# ADC_Chip_And_ISO.net
KiCad netlist of a schematic drawn in Altium Designer
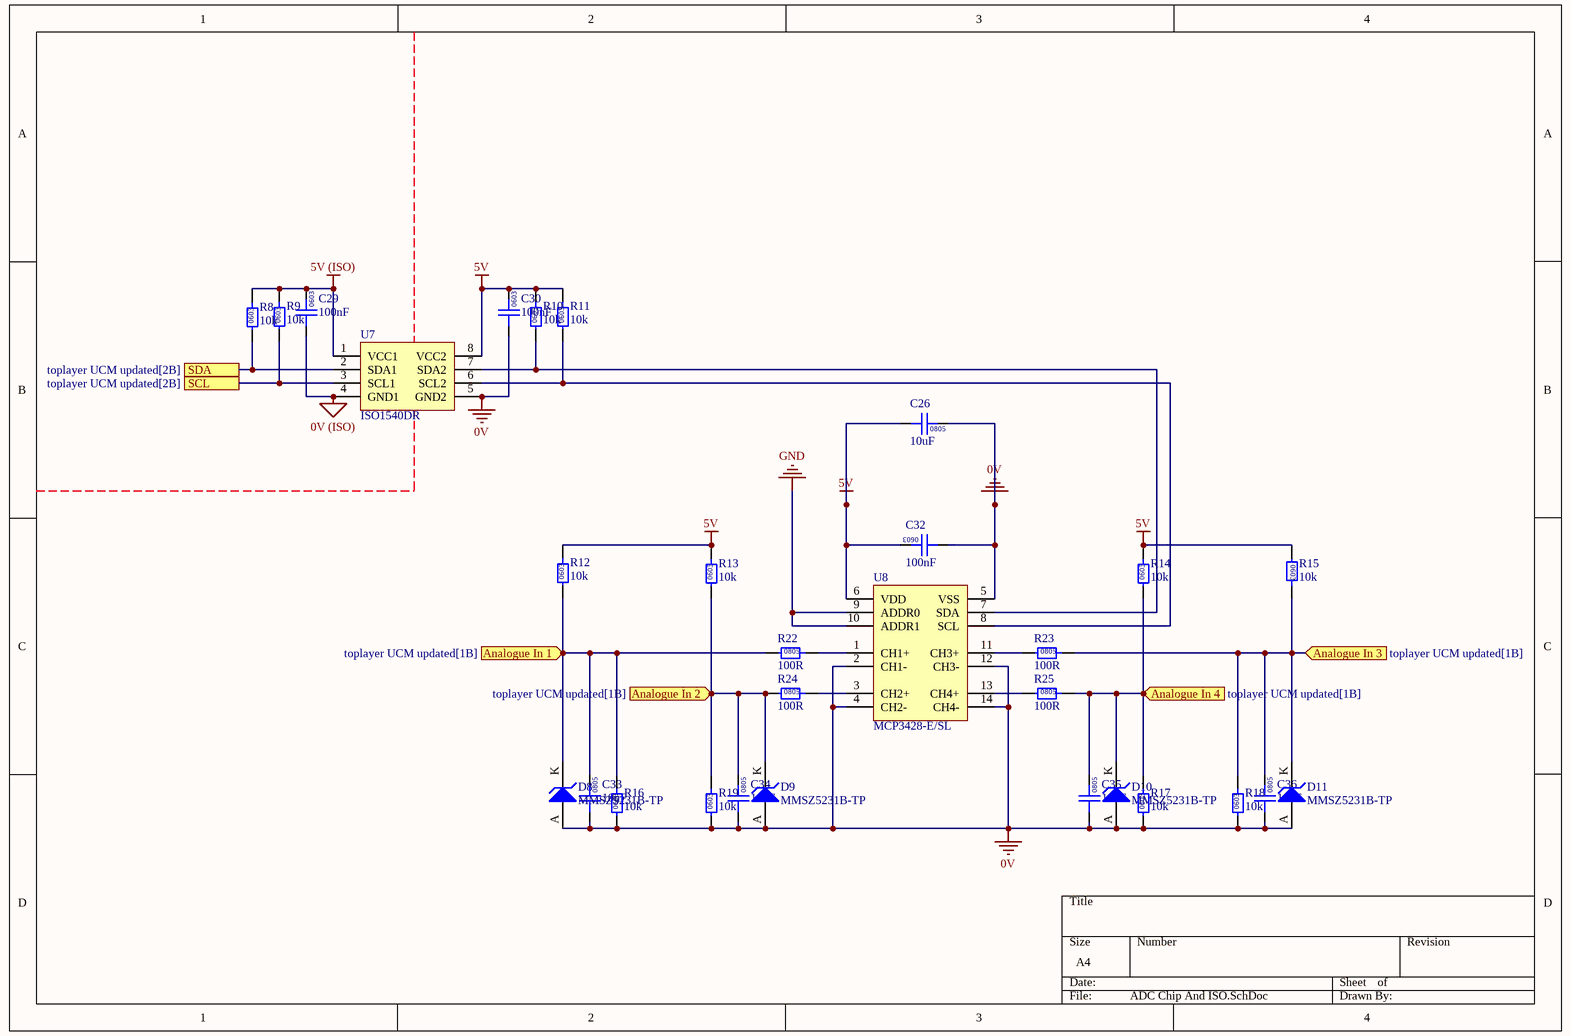
[diagram p0: ADC Chip And ISO.SchDoc]

(export (version "E")
  (design (tool "Eeschema 10.0.6"))
  (components
    (comp (ref "C26")
      (value "10uF")
      (footprint "0805")
      (fields
        (field (name "PART NUMBER") "GRM21BR6YA106KE43L")
        (field (name "MANUFACTURER") "muRata")
        (field (name "TOLERANCE") "10%")
      )
      (libsource (lib "ts_standard_library") (part "Capacitor 0805"))
    )
    (comp (ref "C29")
      (value "100nF")
      (footprint "0603")
      (fields
        (field (name "PART NUMBER") "GCM188L81H104KA57D")
        (field (name "MANUFACTURER") "muRata")
        (field (name "TOLERANCE") "±10%")
      )
      (libsource (lib "ts_standard_library") (part "Capacitor 0603"))
    )
    (comp (ref "C30")
      (value "100nF")
      (footprint "0603")
      (fields
        (field (name "PART NUMBER") "GCM188L81H104KA57D")
        (field (name "MANUFACTURER") "muRata")
        (field (name "TOLERANCE") "±10%")
      )
      (libsource (lib "ts_standard_library") (part "Capacitor 0603"))
    )
    (comp (ref "C32")
      (value "100nF")
      (footprint "0603")
      (fields
        (field (name "PART NUMBER") "GCM188L81H104KA57D")
        (field (name "MANUFACTURER") "muRata")
        (field (name "TOLERANCE") "±10%")
      )
      (libsource (lib "ts_standard_library") (part "Capacitor 0603"))
    )
    (comp (ref "C33")
      (value "10uF")
      (footprint "0805")
      (fields
        (field (name "PART NUMBER") "GRM21BR6YA106KE43L")
        (field (name "MANUFACTURER") "muRata")
        (field (name "TOLERANCE") "10%")
      )
      (libsource (lib "ts_standard_library") (part "Capacitor 0805"))
    )
    (comp (ref "C34")
      (value "10uF")
      (footprint "0805")
      (fields
        (field (name "PART NUMBER") "GRM21BR6YA106KE43L")
        (field (name "MANUFACTURER") "muRata")
        (field (name "TOLERANCE") "10%")
      )
      (libsource (lib "ts_standard_library") (part "Capacitor 0805"))
    )
    (comp (ref "C35")
      (value "10uF")
      (footprint "0805")
      (fields
        (field (name "PART NUMBER") "GRM21BR6YA106KE43L")
        (field (name "MANUFACTURER") "muRata")
        (field (name "TOLERANCE") "10%")
      )
      (libsource (lib "ts_standard_library") (part "Capacitor 0805"))
    )
    (comp (ref "C36")
      (value "10uF")
      (footprint "0805")
      (fields
        (field (name "PART NUMBER") "GRM21BR6YA106KE43L")
        (field (name "MANUFACTURER") "muRata")
        (field (name "TOLERANCE") "10%")
      )
      (libsource (lib "ts_standard_library") (part "Capacitor 0805"))
    )
    (comp (ref "D8")
      (value "MMSZ5231B-TP")
      (footprint "SOD-123 Diode")
      (description "Zener Diode 5.1V 500mW ±5% Surface Mount SOD-123")
      (fields
        (field (name "MANUFACTURER") "On Semiconductor")
        (field (name "DIGIKEY PART NUMBER") "MMSZ5231B-TPMSCT-ND")
      )
      (libsource (lib "ts_20-standard-library") (part "Zener Diode"))
    )
    (comp (ref "D9")
      (value "MMSZ5231B-TP")
      (footprint "SOD-123 Diode")
      (description "Zener Diode 5.1V 500mW ±5% Surface Mount SOD-123")
      (fields
        (field (name "MANUFACTURER") "On Semiconductor")
        (field (name "DIGIKEY PART NUMBER") "MMSZ5231B-TPMSCT-ND")
      )
      (libsource (lib "ts_20-standard-library") (part "Zener Diode"))
    )
    (comp (ref "D10")
      (value "MMSZ5231B-TP")
      (footprint "SOD-123 Diode")
      (description "Zener Diode 5.1V 500mW ±5% Surface Mount SOD-123")
      (fields
        (field (name "MANUFACTURER") "On Semiconductor")
        (field (name "DIGIKEY PART NUMBER") "MMSZ5231B-TPMSCT-ND")
      )
      (libsource (lib "ts_20-standard-library") (part "Zener Diode"))
    )
    (comp (ref "D11")
      (value "MMSZ5231B-TP")
      (footprint "SOD-123 Diode")
      (description "Zener Diode 5.1V 500mW ±5% Surface Mount SOD-123")
      (fields
        (field (name "MANUFACTURER") "On Semiconductor")
        (field (name "DIGIKEY PART NUMBER") "MMSZ5231B-TPMSCT-ND")
      )
      (libsource (lib "ts_20-standard-library") (part "Zener Diode"))
    )
    (comp (ref "R8")
      (value "10k")
      (footprint "0603")
      (fields
        (field (name "PART NUMBER") "RC0603FR-0710KL")
        (field (name "MANUFACTURER") "YAGEO")
        (field (name "TOLERANCE") "0.01")
      )
      (libsource (lib "ts_standard_library") (part "Resistor 0603"))
    )
    (comp (ref "R9")
      (value "10k")
      (footprint "0603")
      (fields
        (field (name "PART NUMBER") "RC0603FR-0710KL")
        (field (name "MANUFACTURER") "YAGEO")
        (field (name "TOLERANCE") "0.01")
      )
      (libsource (lib "ts_standard_library") (part "Resistor 0603"))
    )
    (comp (ref "R10")
      (value "10k")
      (footprint "0603")
      (fields
        (field (name "PART NUMBER") "RC0603FR-0710KL")
        (field (name "MANUFACTURER") "YAGEO")
        (field (name "TOLERANCE") "0.01")
      )
      (libsource (lib "ts_standard_library") (part "Resistor 0603"))
    )
    (comp (ref "R11")
      (value "10k")
      (footprint "0603")
      (fields
        (field (name "PART NUMBER") "RC0603FR-0710KL")
        (field (name "MANUFACTURER") "YAGEO")
        (field (name "TOLERANCE") "0.01")
      )
      (libsource (lib "ts_standard_library") (part "Resistor 0603"))
    )
    (comp (ref "R12")
      (value "10k")
      (footprint "0603")
      (fields
        (field (name "PART NUMBER") "RC0603FR-0710KL")
        (field (name "MANUFACTURER") "YAGEO")
        (field (name "TOLERANCE") "0.01")
      )
      (libsource (lib "ts_standard_library") (part "Resistor 0603"))
    )
    (comp (ref "R13")
      (value "10k")
      (footprint "0603")
      (fields
        (field (name "PART NUMBER") "RC0603FR-0710KL")
        (field (name "MANUFACTURER") "YAGEO")
        (field (name "TOLERANCE") "0.01")
      )
      (libsource (lib "ts_standard_library") (part "Resistor 0603"))
    )
    (comp (ref "R14")
      (value "10k")
      (footprint "VB 0207")
      (fields
        (field (name "PART NUMBER") "RC0603FR-0710KL")
        (field (name "MANUFACTURER") "YAGEO")
        (field (name "TOLERANCE") "0.01")
      )
      (libsource (lib "ts_standard_library") (part "Resistor 0603"))
    )
    (comp (ref "R15")
      (value "10k")
      (footprint "VB 0207")
      (fields
        (field (name "PART NUMBER") "RC0603FR-0710KL")
        (field (name "MANUFACTURER") "YAGEO")
        (field (name "TOLERANCE") "0.01")
      )
      (libsource (lib "ts_standard_library") (part "Resistor 0603"))
    )
    (comp (ref "R16")
      (value "10k")
      (footprint "0603")
      (fields
        (field (name "PART NUMBER") "RC0603FR-0710KL")
        (field (name "MANUFACTURER") "YAGEO")
        (field (name "TOLERANCE") "0.01")
      )
      (libsource (lib "ts_standard_library") (part "Resistor 0603"))
    )
    (comp (ref "R17")
      (value "10k")
      (footprint "0603")
      (fields
        (field (name "PART NUMBER") "RC0603FR-0710KL")
        (field (name "MANUFACTURER") "YAGEO")
        (field (name "TOLERANCE") "0.01")
      )
      (libsource (lib "ts_standard_library") (part "Resistor 0603"))
    )
    (comp (ref "R18")
      (value "10k")
      (footprint "0603")
      (fields
        (field (name "PART NUMBER") "RC0603FR-0710KL")
        (field (name "MANUFACTURER") "YAGEO")
        (field (name "TOLERANCE") "0.01")
      )
      (libsource (lib "ts_standard_library") (part "Resistor 0603"))
    )
    (comp (ref "R19")
      (value "10k")
      (footprint "0603")
      (fields
        (field (name "PART NUMBER") "RC0603FR-0710KL")
        (field (name "MANUFACTURER") "YAGEO")
        (field (name "TOLERANCE") "0.01")
      )
      (libsource (lib "ts_standard_library") (part "Resistor 0603"))
    )
    (comp (ref "R22")
      (value "100R")
      (footprint "0805")
      (fields
        (field (name "PART NUMBER") "RC0805FR07100RL")
        (field (name "MANUFACTURER") "YAGEO")
        (field (name "TOLERANCE") "0.01")
      )
      (libsource (lib "ts_standard_library") (part "Resistor 0805"))
    )
    (comp (ref "R23")
      (value "100R")
      (footprint "0805")
      (fields
        (field (name "PART NUMBER") "RC0805FR07100RL")
        (field (name "MANUFACTURER") "YAGEO")
        (field (name "TOLERANCE") "0.01")
      )
      (libsource (lib "ts_standard_library") (part "Resistor 0805"))
    )
    (comp (ref "R24")
      (value "100R")
      (footprint "0805")
      (fields
        (field (name "PART NUMBER") "RC0805FR07100RL")
        (field (name "MANUFACTURER") "YAGEO")
        (field (name "TOLERANCE") "0.01")
      )
      (libsource (lib "ts_standard_library") (part "Resistor 0805"))
    )
    (comp (ref "R25")
      (value "100R")
      (footprint "0805")
      (fields
        (field (name "PART NUMBER") "RC0805FR07100RL")
        (field (name "MANUFACTURER") "YAGEO")
        (field (name "TOLERANCE") "0.01")
      )
      (libsource (lib "ts_standard_library") (part "Resistor 0805"))
    )
    (comp (ref "U7")
      (value "ISO1540DR")
      (footprint "TI 8-SOIC")
      (description "I2C Digital Isolator (Multichannel)")
      (fields
        (field (name "MANUFACTURER") "Texas Instruments")
        (field (name "DIGIKEY PART NUMBER") "296-34871-1-ND")
      )
      (libsource (lib "ts_20-standard-library") (part "ISO1540DR"))
    )
    (comp (ref "U8")
      (value "MCP3428-E/SL")
      (footprint "MC 14-SOIC")
      (description "4 Channel I2C ADC, 16 bit")
      (fields
        (field (name "MANUFACTURER") "Microchip Technology")
        (field (name "DIGIKEY PART NUMBER") "MCP3428-E/SL-ND")
      )
      (libsource (lib "ts_20-standard-library") (part "MCP3428-E/SL"))
    )
  )
  (nets
    (net (code "1") (name "/Analogue In 1") (class "Default")
      (node (ref "C33") (pin "2") (pinfunction "2_2") (pintype "passive"))
      (node (ref "D8") (pin "K") (pinfunction "K_K") (pintype "passive"))
      (node (ref "R12") (pin "1") (pinfunction "1_1") (pintype "passive"))
      (node (ref "R16") (pin "2") (pinfunction "2_2") (pintype "passive"))
      (node (ref "R22") (pin "1") (pinfunction "1_1") (pintype "passive"))
    )
    (net (code "2") (name "/Analogue In 2") (class "Default")
      (node (ref "C34") (pin "2") (pinfunction "2_2") (pintype "passive"))
      (node (ref "D9") (pin "K") (pinfunction "K_K") (pintype "passive"))
      (node (ref "R13") (pin "1") (pinfunction "1_1") (pintype "passive"))
      (node (ref "R19") (pin "2") (pinfunction "2_2") (pintype "passive"))
      (node (ref "R24") (pin "1") (pinfunction "1_1") (pintype "passive"))
    )
    (net (code "3") (name "/Analogue In 3") (class "Default")
      (node (ref "C36") (pin "2") (pinfunction "2_2") (pintype "passive"))
      (node (ref "D11") (pin "K") (pinfunction "K_K") (pintype "passive"))
      (node (ref "R15") (pin "2") (pinfunction "2_2") (pintype "passive"))
      (node (ref "R18") (pin "2") (pinfunction "2_2") (pintype "passive"))
      (node (ref "R23") (pin "2") (pinfunction "2_2") (pintype "passive"))
    )
    (net (code "4") (name "/Analogue In 4") (class "Default")
      (node (ref "C35") (pin "2") (pinfunction "2_2") (pintype "passive"))
      (node (ref "D10") (pin "K") (pinfunction "K_K") (pintype "passive"))
      (node (ref "R14") (pin "1") (pinfunction "1_1") (pintype "passive"))
      (node (ref "R17") (pin "2") (pinfunction "2_2") (pintype "passive"))
      (node (ref "R25") (pin "2") (pinfunction "2_2") (pintype "passive"))
    )
    (net (code "5") (name "/SCL") (class "Default")
      (node (ref "R9") (pin "1") (pinfunction "1_1") (pintype "passive"))
      (node (ref "U7") (pin "3") (pinfunction "SCL1_3") (pintype "power_in"))
    )
    (net (code "6") (name "/SDA") (class "Default")
      (node (ref "R8") (pin "1") (pinfunction "1_1") (pintype "passive"))
      (node (ref "U7") (pin "2") (pinfunction "SDA1_2") (pintype "power_in"))
    )
    (net (code "7") (name "0V") (class "Default")
      (node (ref "C26") (pin "2") (pinfunction "2_2") (pintype "passive"))
      (node (ref "C30") (pin "1") (pinfunction "1_1") (pintype "passive"))
      (node (ref "C32") (pin "1") (pinfunction "1_1") (pintype "passive"))
      (node (ref "C33") (pin "1") (pinfunction "1_1") (pintype "passive"))
      (node (ref "C34") (pin "1") (pinfunction "1_1") (pintype "passive"))
      (node (ref "C35") (pin "1") (pinfunction "1_1") (pintype "passive"))
      (node (ref "C36") (pin "1") (pinfunction "1_1") (pintype "passive"))
      (node (ref "D10") (pin "A") (pinfunction "A_A") (pintype "passive"))
      (node (ref "D11") (pin "A") (pinfunction "A_A") (pintype "passive"))
      (node (ref "D8") (pin "A") (pinfunction "A_A") (pintype "passive"))
      (node (ref "D9") (pin "A") (pinfunction "A_A") (pintype "passive"))
      (node (ref "R16") (pin "1") (pinfunction "1_1") (pintype "passive"))
      (node (ref "R17") (pin "1") (pinfunction "1_1") (pintype "passive"))
      (node (ref "R18") (pin "1") (pinfunction "1_1") (pintype "passive"))
      (node (ref "R19") (pin "1") (pinfunction "1_1") (pintype "passive"))
      (node (ref "U7") (pin "5") (pinfunction "GND2_5") (pintype "power_in"))
      (node (ref "U8") (pin "12") (pinfunction "CH3-_12") (pintype "power_in"))
      (node (ref "U8") (pin "14") (pinfunction "CH4-_14") (pintype "power_in"))
      (node (ref "U8") (pin "2") (pinfunction "CH1-_2") (pintype "power_in"))
      (node (ref "U8") (pin "4") (pinfunction "CH2-_4") (pintype "power_in"))
      (node (ref "U8") (pin "5") (pinfunction "VSS_5") (pintype "power_in"))
    )
    (net (code "8") (name "0V (ISO)") (class "Default")
      (node (ref "C29") (pin "1") (pinfunction "1_1") (pintype "passive"))
      (node (ref "U7") (pin "4") (pinfunction "GND1_4") (pintype "power_in"))
    )
    (net (code "9") (name "5V") (class "Default")
      (node (ref "C26") (pin "1") (pinfunction "1_1") (pintype "passive"))
      (node (ref "C30") (pin "2") (pinfunction "2_2") (pintype "passive"))
      (node (ref "C32") (pin "2") (pinfunction "2_2") (pintype "passive"))
      (node (ref "R10") (pin "2") (pinfunction "2_2") (pintype "passive"))
      (node (ref "R11") (pin "2") (pinfunction "2_2") (pintype "passive"))
      (node (ref "R12") (pin "2") (pinfunction "2_2") (pintype "passive"))
      (node (ref "R13") (pin "2") (pinfunction "2_2") (pintype "passive"))
      (node (ref "R14") (pin "2") (pinfunction "2_2") (pintype "passive"))
      (node (ref "R15") (pin "1") (pinfunction "1_1") (pintype "passive"))
      (node (ref "U7") (pin "8") (pinfunction "VCC2_8") (pintype "power_in"))
      (node (ref "U8") (pin "6") (pinfunction "VDD_6") (pintype "power_in"))
    )
    (net (code "10") (name "5V (ISO)") (class "Default")
      (node (ref "C29") (pin "2") (pinfunction "2_2") (pintype "passive"))
      (node (ref "R8") (pin "2") (pinfunction "2_2") (pintype "passive"))
      (node (ref "R9") (pin "2") (pinfunction "2_2") (pintype "passive"))
      (node (ref "U7") (pin "1") (pinfunction "VCC1_1") (pintype "power_in"))
    )
    (net (code "11") (name "GND") (class "Default")
      (node (ref "U8") (pin "10") (pinfunction "ADDR1_10") (pintype "power_in"))
      (node (ref "U8") (pin "9") (pinfunction "ADDR0_9") (pintype "power_in"))
    )
    (net (code "12") (name "Net-(U7-SCL2)") (class "Default")
      (node (ref "R11") (pin "1") (pinfunction "1_1") (pintype "passive"))
      (node (ref "U7") (pin "6") (pinfunction "SCL2_6") (pintype "power_in"))
      (node (ref "U8") (pin "8") (pinfunction "SCL_8") (pintype "power_in"))
    )
    (net (code "13") (name "Net-(U7-SDA2)") (class "Default")
      (node (ref "R10") (pin "1") (pinfunction "1_1") (pintype "passive"))
      (node (ref "U7") (pin "7") (pinfunction "SDA2_7") (pintype "power_in"))
      (node (ref "U8") (pin "7") (pinfunction "SDA_7") (pintype "power_in"))
    )
    (net (code "14") (name "Net-(U8-CH1+)") (class "Default")
      (node (ref "R22") (pin "2") (pinfunction "2_2") (pintype "passive"))
      (node (ref "U8") (pin "1") (pinfunction "CH1+_1") (pintype "power_in"))
    )
    (net (code "15") (name "Net-(U8-CH2+)") (class "Default")
      (node (ref "R24") (pin "2") (pinfunction "2_2") (pintype "passive"))
      (node (ref "U8") (pin "3") (pinfunction "CH2+_3") (pintype "power_in"))
    )
    (net (code "16") (name "Net-(U8-CH3+)") (class "Default")
      (node (ref "R23") (pin "1") (pinfunction "1_1") (pintype "passive"))
      (node (ref "U8") (pin "11") (pinfunction "CH3+_11") (pintype "power_in"))
    )
    (net (code "17") (name "Net-(U8-CH4+)") (class "Default")
      (node (ref "R25") (pin "1") (pinfunction "1_1") (pintype "passive"))
      (node (ref "U8") (pin "13") (pinfunction "CH4+_13") (pintype "power_in"))
    )
  )
)
